# apple_all_pt2.net
KiCad netlist of a schematic drawn in EAGLE
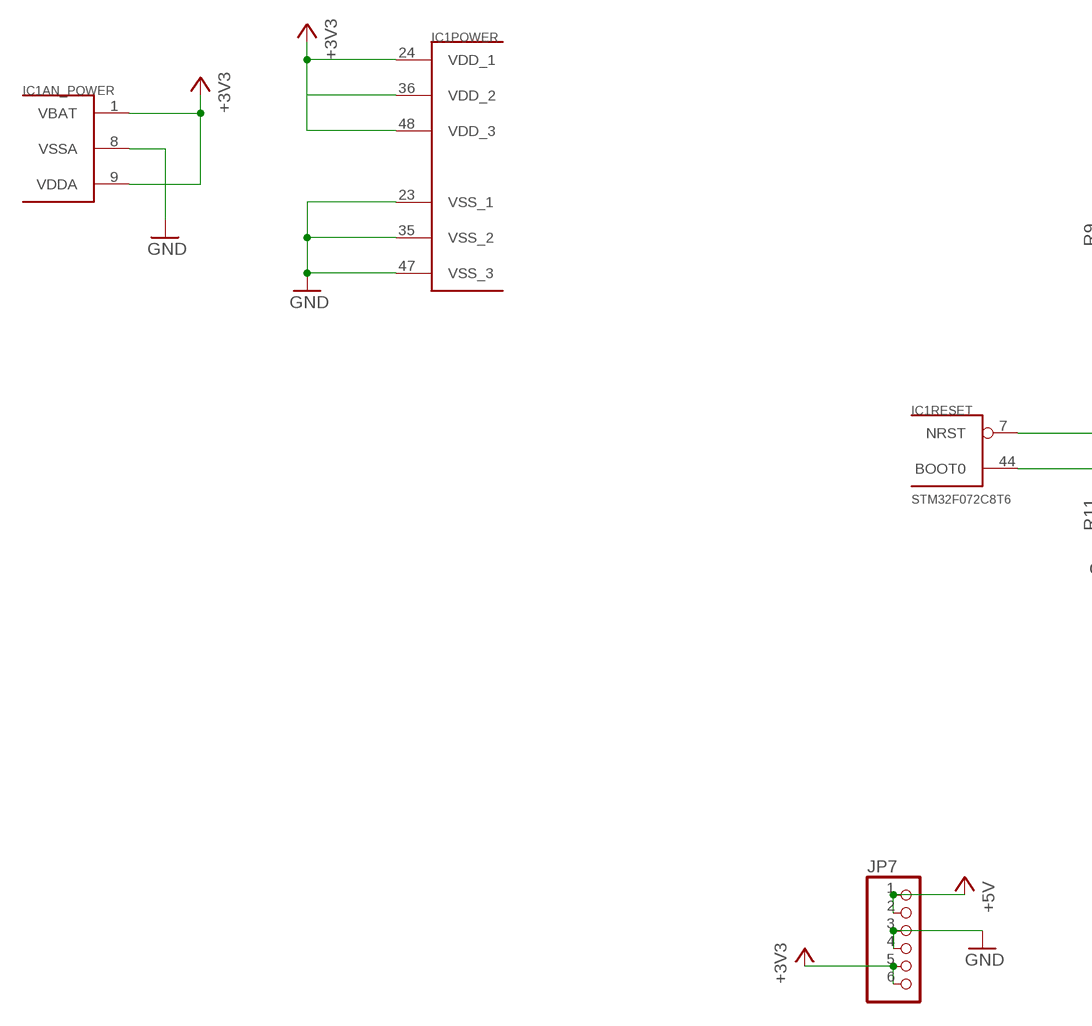
[diagram p0: schematic, sheet 1, part 1 of 2]
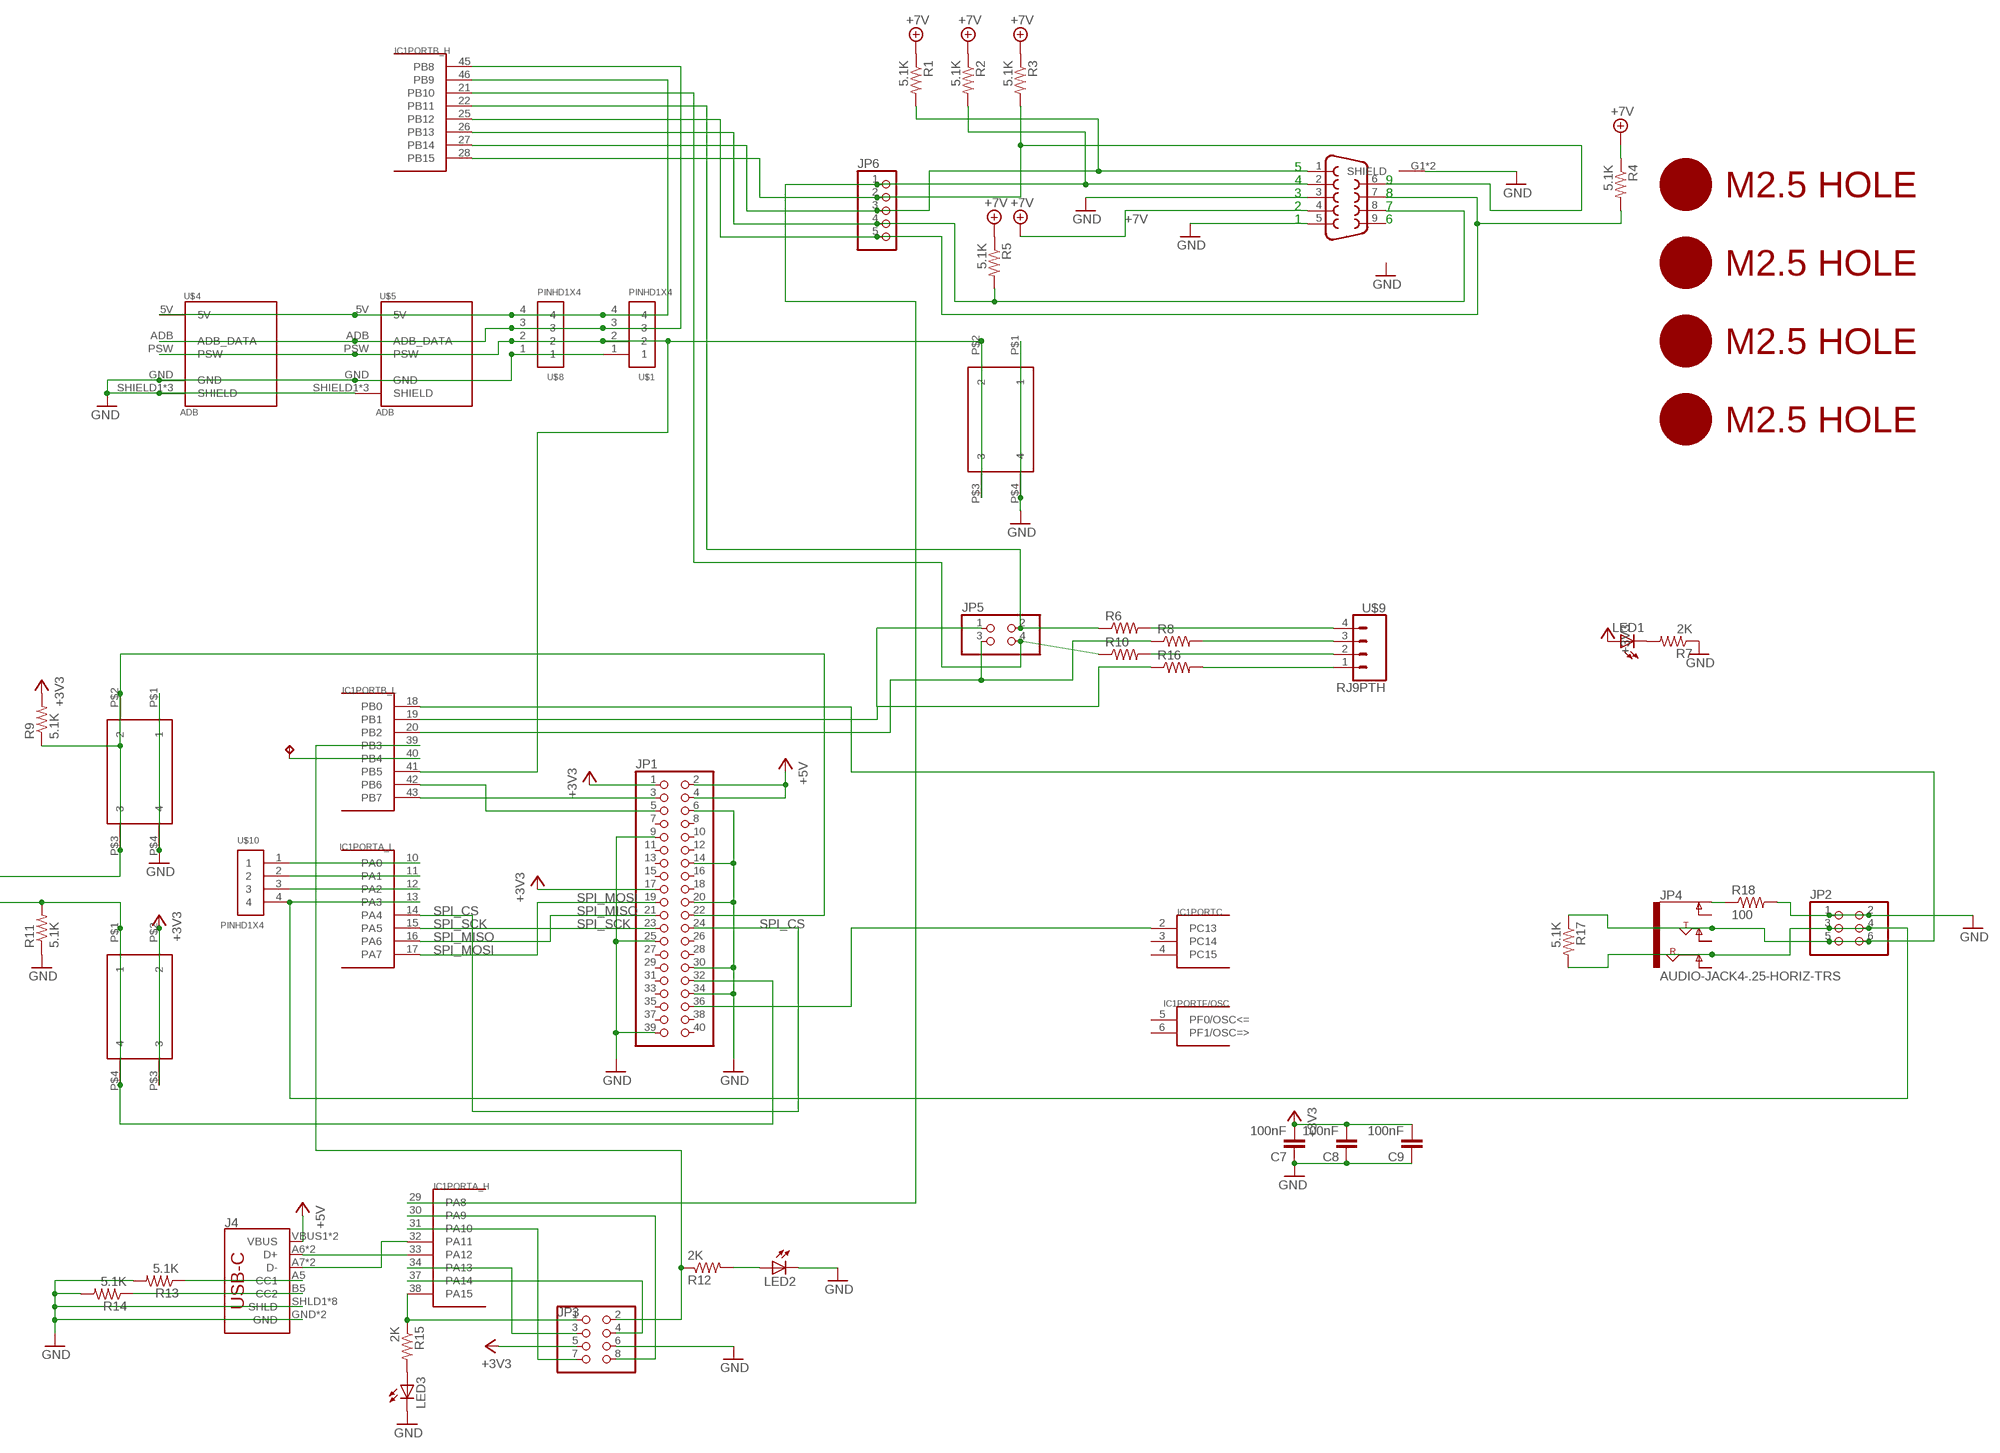
[diagram p1: schematic, sheet 1, part 2 of 2]

(export (version "E")
  (design (tool "Eeschema 10.0.6"))
  (components
    (comp (ref "C7")
      (value "100nF")
      (footprint "eagle-import:0805@1")
      (libsource (lib "eagle-import") (part "CAP0805"))
    )
    (comp (ref "C8")
      (value "100nF")
      (footprint "eagle-import:0805@1")
      (libsource (lib "eagle-import") (part "CAP0805"))
    )
    (comp (ref "C9")
      (value "100nF")
      (footprint "eagle-import:0805@1")
      (libsource (lib "eagle-import") (part "CAP0805"))
    )
    (comp (ref "IC1")
      (value "STM32F072C8T6")
      (footprint "eagle-import:TQFP48")
      (libsource (lib "eagle-import") (part "STM32F072C8T6"))
    )
    (comp (ref "J2")
      (value "DB9FEMALE")
      (footprint "eagle-import:DB9")
      (libsource (lib "eagle-import") (part "DB9FEMALE"))
    )
    (comp (ref "J4")
      (value "USB_C16PIN")
      (footprint "eagle-import:USB-C-16P")
      (libsource (lib "eagle-import") (part "USB_C16PIN"))
    )
    (comp (ref "JP1")
      (value "PINHD-2X20-BIG")
      (footprint "eagle-import:2X20-BIG")
      (libsource (lib "eagle-import") (part "PINHD-2X20-BIG"))
    )
    (comp (ref "JP2")
      (value "PINHD-2X3")
      (footprint "eagle-import:2X03")
      (libsource (lib "eagle-import") (part "PINHD-2X3"))
    )
    (comp (ref "JP3")
      (value "PINHD-2X4")
      (footprint "eagle-import:2X04")
      (libsource (lib "eagle-import") (part "PINHD-2X4"))
    )
    (comp (ref "JP4")
      (value "AUDIO-JACK4-.25-HORIZ-TRS")
      (footprint "eagle-import:AUDIO-JACK-.25-INCH-HORIZ-PTH")
      (libsource (lib "eagle-import") (part "AUDIO-JACK4-.25-HORIZ-TRS"))
    )
    (comp (ref "JP5")
      (value "PINHD-2X2")
      (footprint "eagle-import:2X02")
      (libsource (lib "eagle-import") (part "PINHD-2X2"))
    )
    (comp (ref "JP6")
      (value "PINHD-1X5")
      (footprint "eagle-import:1X05")
      (libsource (lib "eagle-import") (part "PINHD-1X5"))
    )
    (comp (ref "JP7")
      (value "PINHD-1X6CB")
      (footprint "eagle-import:1X06-CLEANBIG")
      (libsource (lib "eagle-import") (part "PINHD-1X6CB"))
    )
    (comp (ref "LED1")
      (value "LEDCHIP-LED0805")
      (footprint "eagle-import:CHIP-LED0805")
      (libsource (lib "eagle-import") (part "LEDCHIP-LED0805"))
    )
    (comp (ref "LED2")
      (value "LEDCHIP-LED0805")
      (footprint "eagle-import:CHIP-LED0805")
      (libsource (lib "eagle-import") (part "LEDCHIP-LED0805"))
    )
    (comp (ref "LED3")
      (value "LEDCHIP-LED0805")
      (footprint "eagle-import:CHIP-LED0805")
      (libsource (lib "eagle-import") (part "LEDCHIP-LED0805"))
    )
    (comp (ref "R1")
      (value "5.1K")
      (footprint "eagle-import:0805")
      (libsource (lib "eagle-import") (part "RESISTOR0805-RES"))
    )
    (comp (ref "R2")
      (value "5.1K")
      (footprint "eagle-import:0805")
      (libsource (lib "eagle-import") (part "RESISTOR0805-RES"))
    )
    (comp (ref "R3")
      (value "5.1K")
      (footprint "eagle-import:0805")
      (libsource (lib "eagle-import") (part "RESISTOR0805-RES"))
    )
    (comp (ref "R4")
      (value "5.1K")
      (footprint "eagle-import:0805")
      (libsource (lib "eagle-import") (part "RESISTOR0805-RES"))
    )
    (comp (ref "R5")
      (value "5.1K")
      (footprint "eagle-import:0805")
      (libsource (lib "eagle-import") (part "RESISTOR0805-RES"))
    )
    (comp (ref "R6")
      (value "50")
      (footprint "eagle-import:0805")
      (libsource (lib "eagle-import") (part "RESISTOR0805-RES"))
    )
    (comp (ref "R7")
      (value "2K")
      (footprint "eagle-import:0805")
      (libsource (lib "eagle-import") (part "RESISTOR0805-RES"))
    )
    (comp (ref "R8")
      (value "50")
      (footprint "eagle-import:0805")
      (libsource (lib "eagle-import") (part "RESISTOR0805-RES"))
    )
    (comp (ref "R9")
      (value "5.1K")
      (footprint "eagle-import:0805")
      (libsource (lib "eagle-import") (part "RESISTOR0805-RES"))
    )
    (comp (ref "R10")
      (value "50")
      (footprint "eagle-import:0805")
      (libsource (lib "eagle-import") (part "RESISTOR0805-RES"))
    )
    (comp (ref "R11")
      (value "5.1K")
      (footprint "eagle-import:0805")
      (libsource (lib "eagle-import") (part "RESISTOR0805-RES"))
    )
    (comp (ref "R12")
      (value "2K")
      (footprint "eagle-import:0805")
      (libsource (lib "eagle-import") (part "RESISTOR0805-RES"))
    )
    (comp (ref "R13")
      (value "5.1K")
      (footprint "eagle-import:0805")
      (libsource (lib "eagle-import") (part "RESISTOR0805-RES"))
    )
    (comp (ref "R14")
      (value "5.1K")
      (footprint "eagle-import:0805")
      (libsource (lib "eagle-import") (part "RESISTOR0805-RES"))
    )
    (comp (ref "R15")
      (value "2K")
      (footprint "eagle-import:0805")
      (libsource (lib "eagle-import") (part "RESISTOR0805-RES"))
    )
    (comp (ref "R16")
      (value "50")
      (footprint "eagle-import:0805")
      (libsource (lib "eagle-import") (part "RESISTOR0805-RES"))
    )
    (comp (ref "R17")
      (value "5.1K")
      (footprint "eagle-import:0805")
      (libsource (lib "eagle-import") (part "RESISTOR0805-RES"))
    )
    (comp (ref "R18")
      (value "100")
      (footprint "eagle-import:0805")
      (libsource (lib "eagle-import") (part "RESISTOR0805-RES"))
    )
    (comp (ref "SW1")
      (value "324_SW")
      (footprint "eagle-import:342_SWICH_FOOT")
      (libsource (lib "eagle-import") (part "324_SW"))
    )
    (comp (ref "SW2")
      (value "324_SW")
      (footprint "eagle-import:342_SWICH_FOOT")
      (libsource (lib "eagle-import") (part "324_SW"))
    )
    (comp (ref "SW3")
      (value "324_SW")
      (footprint "eagle-import:342_SWICH_FOOT")
      (libsource (lib "eagle-import") (part "324_SW"))
    )
    (comp (ref "TP3")
      (value "TPTP12R")
      (footprint "eagle-import:TP12R")
      (libsource (lib "eagle-import") (part "TPTP12R"))
    )
    (comp (ref "U$1")
      (value "PINHD1X4")
      (footprint "eagle-import:1X04-CLEANBIG")
      (libsource (lib "eagle-import") (part "PINHD1X4"))
    )
    (comp (ref "U$2")
      (value "M2.5HOLE")
      (footprint "eagle-import:M2.5HOLE")
      (libsource (lib "eagle-import") (part "M2.5HOLE"))
    )
    (comp (ref "U$3")
      (value "M2.5HOLE")
      (footprint "eagle-import:M2.5HOLE")
      (libsource (lib "eagle-import") (part "M2.5HOLE"))
    )
    (comp (ref "U$4")
      (value "ADB")
      (footprint "eagle-import:DIN4")
      (libsource (lib "eagle-import") (part "ADB"))
    )
    (comp (ref "U$5")
      (value "ADB")
      (footprint "eagle-import:DIN4")
      (libsource (lib "eagle-import") (part "ADB"))
    )
    (comp (ref "U$6")
      (value "M2.5HOLE")
      (footprint "eagle-import:M2.5HOLE")
      (libsource (lib "eagle-import") (part "M2.5HOLE"))
    )
    (comp (ref "U$7")
      (value "M2.5HOLE")
      (footprint "eagle-import:M2.5HOLE")
      (libsource (lib "eagle-import") (part "M2.5HOLE"))
    )
    (comp (ref "U$8")
      (value "PINHD1X4")
      (footprint "eagle-import:1X04-CLEANBIG")
      (libsource (lib "eagle-import") (part "PINHD1X4"))
    )
    (comp (ref "U$9")
      (value "RJ9PTH")
      (footprint "eagle-import:RJ9")
      (libsource (lib "eagle-import") (part "RJ9PTH"))
    )
    (comp (ref "U$10")
      (value "PINHD1X4")
      (footprint "eagle-import:1X04-CLEANBIG")
      (libsource (lib "eagle-import") (part "PINHD1X4"))
    )
  )
  (nets
    (net (code "1") (name "+3V3") (class "Default")
      (node (ref "C7") (pin "2") (pinfunction "2_2") (pintype "passive"))
      (node (ref "C8") (pin "2") (pinfunction "2_2") (pintype "passive"))
      (node (ref "C9") (pin "2") (pinfunction "2_2") (pintype "passive"))
      (node (ref "IC1") (pin "1") (pinfunction "VBAT_1") (pintype "power_in"))
      (node (ref "IC1") (pin "24") (pinfunction "VDD_1_24") (pintype "power_in"))
      (node (ref "IC1") (pin "36") (pinfunction "VDD_2_36") (pintype "power_in"))
      (node (ref "IC1") (pin "48") (pinfunction "VDD_3_48") (pintype "power_in"))
      (node (ref "IC1") (pin "9") (pinfunction "VDDA_9") (pintype "power_in"))
      (node (ref "JP1") (pin "1") (pinfunction "1_1") (pintype "passive"))
      (node (ref "JP1") (pin "17") (pinfunction "17_17") (pintype "passive"))
      (node (ref "JP3") (pin "5") (pinfunction "5_5") (pintype "passive"))
      (node (ref "JP7") (pin "5") (pinfunction "5_5") (pintype "passive"))
      (node (ref "JP7") (pin "6") (pinfunction "6_6") (pintype "passive"))
      (node (ref "LED1") (pin "A") (pinfunction "A_A") (pintype "passive"))
      (node (ref "R9") (pin "2") (pinfunction "2_2") (pintype "passive"))
      (node (ref "SW2") (pin "P$2") (pinfunction "2_P$2") (pintype "bidirectional"))
      (node (ref "SW2") (pin "P$3") (pinfunction "3_P$3") (pintype "bidirectional"))
    )
    (net (code "2") (name "+5V") (class "Default")
      (node (ref "J4") (pin "VBUS1") (pinfunction "VBUS_VBUS1") (pintype "bidirectional"))
      (node (ref "J4") (pin "VBUS2") (pinfunction "VBUS_VBUS2") (pintype "bidirectional"))
      (node (ref "JP1") (pin "2") (pinfunction "2_2") (pintype "passive"))
      (node (ref "JP1") (pin "4") (pinfunction "4_4") (pintype "passive"))
      (node (ref "JP7") (pin "1") (pinfunction "1_1") (pintype "passive"))
      (node (ref "JP7") (pin "2") (pinfunction "2_2") (pintype "passive"))
    )
    (net (code "3") (name "+7V") (class "Default")
      (node (ref "J2") (pin "4") (pinfunction "4_4") (pintype "passive"))
      (node (ref "R1") (pin "1") (pinfunction "1_1") (pintype "passive"))
      (node (ref "R2") (pin "1") (pinfunction "1_1") (pintype "passive"))
      (node (ref "R3") (pin "1") (pinfunction "1_1") (pintype "passive"))
      (node (ref "R4") (pin "1") (pinfunction "1_1") (pintype "passive"))
      (node (ref "R5") (pin "1") (pinfunction "1_1") (pintype "passive"))
    )
    (net (code "4") (name "/SPI_CS") (class "Default")
      (node (ref "IC1") (pin "14") (pinfunction "PA4_14") (pintype "bidirectional"))
      (node (ref "JP1") (pin "24") (pinfunction "24_24") (pintype "passive"))
    )
    (net (code "5") (name "/SPI_MISO") (class "Default")
      (node (ref "IC1") (pin "16") (pinfunction "PA6_16") (pintype "bidirectional"))
      (node (ref "JP1") (pin "21") (pinfunction "21_21") (pintype "passive"))
    )
    (net (code "6") (name "/SPI_MOSI") (class "Default")
      (node (ref "IC1") (pin "17") (pinfunction "PA7_17") (pintype "bidirectional"))
      (node (ref "JP1") (pin "19") (pinfunction "19_19") (pintype "passive"))
    )
    (net (code "7") (name "/SPI_SCK") (class "Default")
      (node (ref "IC1") (pin "15") (pinfunction "PA5_15") (pintype "bidirectional"))
      (node (ref "JP1") (pin "23") (pinfunction "23_23") (pintype "passive"))
    )
    (net (code "8") (name "GND") (class "Default")
      (node (ref "C7") (pin "1") (pinfunction "1_1") (pintype "passive"))
      (node (ref "C8") (pin "1") (pinfunction "1_1") (pintype "passive"))
      (node (ref "C9") (pin "1") (pinfunction "1_1") (pintype "passive"))
      (node (ref "IC1") (pin "23") (pinfunction "VSS_1_23") (pintype "power_in"))
      (node (ref "IC1") (pin "35") (pinfunction "VSS_2_35") (pintype "power_in"))
      (node (ref "IC1") (pin "47") (pinfunction "VSS_3_47") (pintype "power_in"))
      (node (ref "IC1") (pin "8") (pinfunction "VSSA_8") (pintype "power_in"))
      (node (ref "J2") (pin "3") (pinfunction "3_3") (pintype "passive"))
      (node (ref "J2") (pin "5") (pinfunction "5_5") (pintype "passive"))
      (node (ref "J2") (pin "G1") (pinfunction "SHIELD_G1") (pintype "bidirectional"))
      (node (ref "J2") (pin "G2") (pinfunction "SHIELD_G2") (pintype "bidirectional"))
      (node (ref "J4") (pin "GND") (pinfunction "GND_GND") (pintype "bidirectional"))
      (node (ref "J4") (pin "GND2") (pinfunction "GND_GND2") (pintype "bidirectional"))
      (node (ref "J4") (pin "SHLD1") (pinfunction "SHLD_SHLD1") (pintype "bidirectional"))
      (node (ref "J4") (pin "SHLD2") (pinfunction "SHLD_SHLD2") (pintype "bidirectional"))
      (node (ref "J4") (pin "SHLD3") (pinfunction "SHLD_SHLD3") (pintype "bidirectional"))
      (node (ref "J4") (pin "SHLD4") (pinfunction "SHLD_SHLD4") (pintype "bidirectional"))
      (node (ref "J4") (pin "SHLD5") (pinfunction "SHLD_SHLD5") (pintype "bidirectional"))
      (node (ref "J4") (pin "SHLD6") (pinfunction "SHLD_SHLD6") (pintype "bidirectional"))
      (node (ref "J4") (pin "SHLD7") (pinfunction "SHLD_SHLD7") (pintype "bidirectional"))
      (node (ref "J4") (pin "SHLD8") (pinfunction "SHLD_SHLD8") (pintype "bidirectional"))
      (node (ref "JP1") (pin "14") (pinfunction "14_14") (pintype "passive"))
      (node (ref "JP1") (pin "20") (pinfunction "20_20") (pintype "passive"))
      (node (ref "JP1") (pin "25") (pinfunction "25_25") (pintype "passive"))
      (node (ref "JP1") (pin "30") (pinfunction "30_30") (pintype "passive"))
      (node (ref "JP1") (pin "34") (pinfunction "34_34") (pintype "passive"))
      (node (ref "JP1") (pin "39") (pinfunction "39_39") (pintype "passive"))
      (node (ref "JP1") (pin "6") (pinfunction "6_6") (pintype "passive"))
      (node (ref "JP1") (pin "9") (pinfunction "9_9") (pintype "passive"))
      (node (ref "JP2") (pin "1") (pinfunction "1_1") (pintype "passive"))
      (node (ref "JP2") (pin "2") (pinfunction "2_2") (pintype "passive"))
      (node (ref "JP3") (pin "6") (pinfunction "6_6") (pintype "passive"))
      (node (ref "JP7") (pin "3") (pinfunction "3_3") (pintype "passive"))
      (node (ref "JP7") (pin "4") (pinfunction "4_4") (pintype "passive"))
      (node (ref "LED2") (pin "C") (pinfunction "C_C") (pintype "passive"))
      (node (ref "LED3") (pin "C") (pinfunction "C_C") (pintype "passive"))
      (node (ref "R11") (pin "1") (pinfunction "1_1") (pintype "passive"))
      (node (ref "R13") (pin "2") (pinfunction "2_2") (pintype "passive"))
      (node (ref "R14") (pin "2") (pinfunction "2_2") (pintype "passive"))
      (node (ref "R18") (pin "2") (pinfunction "2_2") (pintype "passive"))
      (node (ref "R7") (pin "1") (pinfunction "1_1") (pintype "passive"))
      (node (ref "SW1") (pin "P$1") (pinfunction "1_P$1") (pintype "bidirectional"))
      (node (ref "SW1") (pin "P$4") (pinfunction "4_P$4") (pintype "bidirectional"))
      (node (ref "SW3") (pin "P$1") (pinfunction "1_P$1") (pintype "bidirectional"))
      (node (ref "SW3") (pin "P$4") (pinfunction "4_P$4") (pintype "bidirectional"))
      (node (ref "U$1") (pin "1") (pinfunction "1_1") (pintype "bidirectional"))
      (node (ref "U$4") (pin "GND") (pinfunction "GND_GND") (pintype "bidirectional"))
      (node (ref "U$4") (pin "SHIELD1") (pinfunction "SHIELD_SHIELD1") (pintype "bidirectional"))
      (node (ref "U$4") (pin "SHIELD2") (pinfunction "SHIELD_SHIELD2") (pintype "bidirectional"))
      (node (ref "U$4") (pin "SHIELD3") (pinfunction "SHIELD_SHIELD3") (pintype "bidirectional"))
      (node (ref "U$5") (pin "GND") (pinfunction "GND_GND") (pintype "bidirectional"))
      (node (ref "U$5") (pin "SHIELD1") (pinfunction "SHIELD_SHIELD1") (pintype "bidirectional"))
      (node (ref "U$5") (pin "SHIELD2") (pinfunction "SHIELD_SHIELD2") (pintype "bidirectional"))
      (node (ref "U$5") (pin "SHIELD3") (pinfunction "SHIELD_SHIELD3") (pintype "bidirectional"))
      (node (ref "U$8") (pin "1") (pinfunction "1_1") (pintype "bidirectional"))
    )
    (net (code "9") (name "Net-(IC1B-PA8)") (class "Default")
      (node (ref "IC1") (pin "29") (pinfunction "PA8_29") (pintype "bidirectional"))
      (node (ref "J2") (pin "2") (pinfunction "2_2") (pintype "passive"))
      (node (ref "JP6") (pin "1") (pinfunction "1_1") (pintype "passive"))
      (node (ref "R2") (pin "2") (pinfunction "2_2") (pintype "passive"))
    )
    (net (code "10") (name "Net-(IC1B-PA9)") (class "Default")
      (node (ref "IC1") (pin "30") (pinfunction "PA9_30") (pintype "bidirectional"))
      (node (ref "JP3") (pin "8") (pinfunction "8_8") (pintype "passive"))
    )
    (net (code "11") (name "Net-(IC1B-PA10)") (class "Default")
      (node (ref "IC1") (pin "31") (pinfunction "PA10_31") (pintype "bidirectional"))
      (node (ref "JP3") (pin "7") (pinfunction "7_7") (pintype "passive"))
    )
    (net (code "12") (name "Net-(IC1B-PA11)") (class "Default")
      (node (ref "IC1") (pin "32") (pinfunction "PA11_32") (pintype "bidirectional"))
      (node (ref "J4") (pin "A7") (pinfunction "D-_A7") (pintype "bidirectional"))
      (node (ref "J4") (pin "B7") (pinfunction "D-_B7") (pintype "bidirectional"))
    )
    (net (code "13") (name "Net-(IC1B-PA12)") (class "Default")
      (node (ref "IC1") (pin "33") (pinfunction "PA12_33") (pintype "bidirectional"))
      (node (ref "J4") (pin "A6") (pinfunction "D+_A6") (pintype "bidirectional"))
      (node (ref "J4") (pin "B6") (pinfunction "D+_B6") (pintype "bidirectional"))
    )
    (net (code "14") (name "Net-(IC1B-PA13)") (class "Default")
      (node (ref "IC1") (pin "34") (pinfunction "PA13_34") (pintype "bidirectional"))
      (node (ref "JP3") (pin "3") (pinfunction "3_3") (pintype "passive"))
    )
    (net (code "15") (name "Net-(IC1B-PA14)") (class "Default")
      (node (ref "IC1") (pin "37") (pinfunction "PA14_37") (pintype "bidirectional"))
      (node (ref "JP3") (pin "4") (pinfunction "4_4") (pintype "passive"))
    )
    (net (code "16") (name "Net-(IC1B-PA15)") (class "Default")
      (node (ref "IC1") (pin "38") (pinfunction "PA15_38") (pintype "bidirectional"))
      (node (ref "JP3") (pin "1") (pinfunction "1_1") (pintype "passive"))
      (node (ref "R15") (pin "1") (pinfunction "1_1") (pintype "passive"))
    )
    (net (code "17") (name "Net-(IC1C-PA0)") (class "Default")
      (node (ref "IC1") (pin "10") (pinfunction "PA0_10") (pintype "bidirectional"))
      (node (ref "U$10") (pin "1") (pinfunction "1_1") (pintype "bidirectional"))
    )
    (net (code "18") (name "Net-(IC1C-PA1)") (class "Default")
      (node (ref "IC1") (pin "11") (pinfunction "PA1_11") (pintype "bidirectional"))
      (node (ref "U$10") (pin "2") (pinfunction "2_2") (pintype "bidirectional"))
    )
    (net (code "19") (name "Net-(IC1C-PA2)") (class "Default")
      (node (ref "IC1") (pin "12") (pinfunction "PA2_12") (pintype "bidirectional"))
      (node (ref "U$10") (pin "3") (pinfunction "3_3") (pintype "bidirectional"))
    )
    (net (code "20") (name "Net-(IC1C-PA3)") (class "Default")
      (node (ref "IC1") (pin "13") (pinfunction "PA3_13") (pintype "bidirectional"))
      (node (ref "JP2") (pin "3") (pinfunction "3_3") (pintype "passive"))
      (node (ref "JP2") (pin "4") (pinfunction "4_4") (pintype "passive"))
      (node (ref "JP4") (pin "RING") (pinfunction "RING_RING") (pintype "bidirectional"))
      (node (ref "R17") (pin "2") (pinfunction "2_2") (pintype "passive"))
      (node (ref "U$10") (pin "4") (pinfunction "4_4") (pintype "bidirectional"))
    )
    (net (code "21") (name "Net-(IC1D-PB8)") (class "Default")
      (node (ref "IC1") (pin "45") (pinfunction "PB8_45") (pintype "bidirectional"))
      (node (ref "U$1") (pin "3") (pinfunction "3_3") (pintype "bidirectional"))
      (node (ref "U$4") (pin "ADB") (pinfunction "ADB_DATA_ADB") (pintype "bidirectional"))
      (node (ref "U$5") (pin "ADB") (pinfunction "ADB_DATA_ADB") (pintype "bidirectional"))
      (node (ref "U$8") (pin "3") (pinfunction "3_3") (pintype "bidirectional"))
    )
    (net (code "22") (name "Net-(IC1D-PB9)") (class "Default")
      (node (ref "IC1") (pin "46") (pinfunction "PB9_46") (pintype "bidirectional"))
      (node (ref "U$1") (pin "4") (pinfunction "4_4") (pintype "bidirectional"))
      (node (ref "U$4") (pin "5V") (pinfunction "5V_5V") (pintype "bidirectional"))
      (node (ref "U$5") (pin "5V") (pinfunction "5V_5V") (pintype "bidirectional"))
      (node (ref "U$8") (pin "4") (pinfunction "4_4") (pintype "bidirectional"))
    )
    (net (code "23") (name "Net-(IC1D-PB10)") (class "Default")
      (node (ref "IC1") (pin "21") (pinfunction "PB10_21") (pintype "bidirectional"))
      (node (ref "JP5") (pin "4") (pinfunction "4_4") (pintype "passive"))
      (node (ref "R10") (pin "1") (pinfunction "1_1") (pintype "passive"))
    )
    (net (code "24") (name "Net-(IC1D-PB11)") (class "Default")
      (node (ref "IC1") (pin "22") (pinfunction "PB11_22") (pintype "bidirectional"))
      (node (ref "JP5") (pin "2") (pinfunction "2_2") (pintype "passive"))
      (node (ref "R6") (pin "1") (pinfunction "1_1") (pintype "passive"))
    )
    (net (code "25") (name "Net-(IC1D-PB12)") (class "Default")
      (node (ref "IC1") (pin "25") (pinfunction "PB12_25") (pintype "bidirectional"))
      (node (ref "J2") (pin "7") (pinfunction "7_7") (pintype "passive"))
      (node (ref "JP6") (pin "5") (pinfunction "5_5") (pintype "passive"))
      (node (ref "R4") (pin "2") (pinfunction "2_2") (pintype "passive"))
    )
    (net (code "26") (name "Net-(IC1D-PB13)") (class "Default")
      (node (ref "IC1") (pin "26") (pinfunction "PB13_26") (pintype "bidirectional"))
      (node (ref "J2") (pin "8") (pinfunction "8_8") (pintype "passive"))
      (node (ref "JP6") (pin "4") (pinfunction "4_4") (pintype "passive"))
      (node (ref "R5") (pin "2") (pinfunction "2_2") (pintype "passive"))
    )
    (net (code "27") (name "Net-(IC1D-PB14)") (class "Default")
      (node (ref "IC1") (pin "27") (pinfunction "PB14_27") (pintype "bidirectional"))
      (node (ref "J2") (pin "1") (pinfunction "1_1") (pintype "passive"))
      (node (ref "JP6") (pin "3") (pinfunction "3_3") (pintype "passive"))
      (node (ref "R1") (pin "2") (pinfunction "2_2") (pintype "passive"))
    )
    (net (code "28") (name "Net-(IC1D-PB15)") (class "Default")
      (node (ref "IC1") (pin "28") (pinfunction "PB15_28") (pintype "bidirectional"))
      (node (ref "J2") (pin "6") (pinfunction "6_6") (pintype "passive"))
      (node (ref "JP6") (pin "2") (pinfunction "2_2") (pintype "passive"))
      (node (ref "R3") (pin "2") (pinfunction "2_2") (pintype "passive"))
    )
    (net (code "29") (name "Net-(IC1E-PB0)") (class "Default")
      (node (ref "IC1") (pin "18") (pinfunction "PB0_18") (pintype "bidirectional"))
      (node (ref "JP2") (pin "5") (pinfunction "5_5") (pintype "passive"))
      (node (ref "JP2") (pin "6") (pinfunction "6_6") (pintype "passive"))
      (node (ref "JP4") (pin "TIP") (pinfunction "TIP_TIP") (pintype "bidirectional"))
      (node (ref "R17") (pin "1") (pinfunction "1_1") (pintype "passive"))
    )
    (net (code "30") (name "Net-(IC1E-PB1)") (class "Default")
      (node (ref "IC1") (pin "19") (pinfunction "PB1_19") (pintype "bidirectional"))
      (node (ref "JP5") (pin "1") (pinfunction "1_1") (pintype "passive"))
      (node (ref "R16") (pin "1") (pinfunction "1_1") (pintype "passive"))
    )
    (net (code "31") (name "Net-(IC1E-PB2)") (class "Default")
      (node (ref "IC1") (pin "20") (pinfunction "PB2_20") (pintype "bidirectional"))
      (node (ref "JP5") (pin "3") (pinfunction "3_3") (pintype "passive"))
      (node (ref "R8") (pin "1") (pinfunction "1_1") (pintype "passive"))
    )
    (net (code "32") (name "Net-(IC1E-PB3)") (class "Default")
      (node (ref "IC1") (pin "39") (pinfunction "PB3_39") (pintype "bidirectional"))
      (node (ref "JP3") (pin "2") (pinfunction "2_2") (pintype "passive"))
      (node (ref "R12") (pin "1") (pinfunction "1_1") (pintype "passive"))
    )
    (net (code "33") (name "Net-(IC1E-PB4)") (class "Default")
      (node (ref "IC1") (pin "40") (pinfunction "PB4_40") (pintype "bidirectional"))
      (node (ref "TP3") (pin "TP") (pinfunction "TP_TP") (pintype "input"))
    )
    (net (code "34") (name "Net-(IC1E-PB5)") (class "Default")
      (node (ref "IC1") (pin "41") (pinfunction "PB5_41") (pintype "bidirectional"))
      (node (ref "SW3") (pin "P$2") (pinfunction "2_P$2") (pintype "bidirectional"))
      (node (ref "SW3") (pin "P$3") (pinfunction "3_P$3") (pintype "bidirectional"))
      (node (ref "U$1") (pin "2") (pinfunction "2_2") (pintype "bidirectional"))
      (node (ref "U$4") (pin "PSW") (pinfunction "PSW_PSW") (pintype "bidirectional"))
      (node (ref "U$5") (pin "PSW") (pinfunction "PSW_PSW") (pintype "bidirectional"))
      (node (ref "U$8") (pin "2") (pinfunction "2_2") (pintype "bidirectional"))
    )
    (net (code "35") (name "Net-(IC1E-PB6)") (class "Default")
      (node (ref "IC1") (pin "42") (pinfunction "PB6_42") (pintype "bidirectional"))
      (node (ref "JP1") (pin "5") (pinfunction "5_5") (pintype "passive"))
    )
    (net (code "36") (name "Net-(IC1E-PB7)") (class "Default")
      (node (ref "IC1") (pin "43") (pinfunction "PB7_43") (pintype "bidirectional"))
      (node (ref "JP1") (pin "3") (pinfunction "3_3") (pintype "passive"))
    )
    (net (code "37") (name "Net-(IC1F-PC13)") (class "Default")
      (node (ref "IC1") (pin "2") (pinfunction "PC13_2") (pintype "bidirectional"))
      (node (ref "JP1") (pin "36") (pinfunction "36_36") (pintype "passive"))
    )
    (net (code "38") (name "Net-(IC1I-BOOT0)") (class "Default")
      (node (ref "IC1") (pin "44") (pinfunction "BOOT0_44") (pintype "input"))
      (node (ref "JP1") (pin "32") (pinfunction "32_32") (pintype "passive"))
      (node (ref "R11") (pin "2") (pinfunction "2_2") (pintype "passive"))
      (node (ref "SW2") (pin "P$1") (pinfunction "1_P$1") (pintype "bidirectional"))
      (node (ref "SW2") (pin "P$4") (pinfunction "4_P$4") (pintype "bidirectional"))
    )
    (net (code "39") (name "Net-(IC1I-NRST)") (class "Default")
      (node (ref "IC1") (pin "7") (pinfunction "NRST_7") (pintype "input"))
      (node (ref "JP1") (pin "22") (pinfunction "22_22") (pintype "passive"))
      (node (ref "R9") (pin "1") (pinfunction "1_1") (pintype "passive"))
      (node (ref "SW1") (pin "P$2") (pinfunction "2_P$2") (pintype "bidirectional"))
      (node (ref "SW1") (pin "P$3") (pinfunction "3_P$3") (pintype "bidirectional"))
    )
    (net (code "40") (name "Net-(J4-CC1)") (class "Default")
      (node (ref "J4") (pin "A5") (pinfunction "CC1_A5") (pintype "bidirectional"))
      (node (ref "R13") (pin "1") (pinfunction "1_1") (pintype "passive"))
    )
    (net (code "41") (name "Net-(J4-CC2)") (class "Default")
      (node (ref "J4") (pin "B5") (pinfunction "CC2_B5") (pintype "bidirectional"))
      (node (ref "R14") (pin "1") (pinfunction "1_1") (pintype "passive"))
    )
    (net (code "42") (name "Net-(JP4-EARTH)") (class "Default")
      (node (ref "JP4") (pin "SLEEVE") (pinfunction "EARTH_SLEEVE") (pintype "bidirectional"))
      (node (ref "R18") (pin "1") (pinfunction "1_1") (pintype "passive"))
    )
    (net (code "43") (name "Net-(LED1-PadC)") (class "Default")
      (node (ref "LED1") (pin "C") (pinfunction "C_C") (pintype "passive"))
      (node (ref "R7") (pin "2") (pinfunction "2_2") (pintype "passive"))
    )
    (net (code "44") (name "Net-(LED2-PadA)") (class "Default")
      (node (ref "LED2") (pin "A") (pinfunction "A_A") (pintype "passive"))
      (node (ref "R12") (pin "2") (pinfunction "2_2") (pintype "passive"))
    )
    (net (code "45") (name "Net-(LED3-PadA)") (class "Default")
      (node (ref "LED3") (pin "A") (pinfunction "A_A") (pintype "passive"))
      (node (ref "R15") (pin "2") (pinfunction "2_2") (pintype "passive"))
    )
    (net (code "46") (name "Net-(R6-Pad2)") (class "Default")
      (node (ref "R6") (pin "2") (pinfunction "2_2") (pintype "passive"))
      (node (ref "U$9") (pin "4") (pinfunction "4_4") (pintype "passive"))
    )
    (net (code "47") (name "Net-(R8-Pad2)") (class "Default")
      (node (ref "R8") (pin "2") (pinfunction "2_2") (pintype "passive"))
      (node (ref "U$9") (pin "3") (pinfunction "3_3") (pintype "passive"))
    )
    (net (code "48") (name "Net-(R10-Pad2)") (class "Default")
      (node (ref "R10") (pin "2") (pinfunction "2_2") (pintype "passive"))
      (node (ref "U$9") (pin "2") (pinfunction "2_2") (pintype "passive"))
    )
    (net (code "49") (name "Net-(R16-Pad2)") (class "Default")
      (node (ref "R16") (pin "2") (pinfunction "2_2") (pintype "passive"))
      (node (ref "U$9") (pin "1") (pinfunction "1_1") (pintype "passive"))
    )
    (net (code "50") (name "unconnected-(IC1F-PC14-Pad3)") (class "Default")
      (node (ref "IC1") (pin "3") (pinfunction "PC14_3") (pintype "bidirectional"))
    )
    (net (code "51") (name "unconnected-(IC1F-PC15-Pad4)") (class "Default")
      (node (ref "IC1") (pin "4") (pinfunction "PC15_4") (pintype "bidirectional"))
    )
    (net (code "52") (name "unconnected-(IC1G-PF0{slash}OSC<=-Pad5)") (class "Default")
      (node (ref "IC1") (pin "5") (pinfunction "PF0/OSC<=_5") (pintype "bidirectional"))
    )
    (net (code "53") (name "unconnected-(IC1G-PF1{slash}OSC=>-Pad6)") (class "Default")
      (node (ref "IC1") (pin "6") (pinfunction "PF1/OSC=>_6") (pintype "bidirectional"))
    )
    (net (code "54") (name "unconnected-(J2-Pad9)") (class "Default")
      (node (ref "J2") (pin "9") (pinfunction "9_9") (pintype "passive"))
    )
    (net (code "55") (name "unconnected-(JP1-Pad7)") (class "Default")
      (node (ref "JP1") (pin "7") (pinfunction "7_7") (pintype "passive"))
    )
    (net (code "56") (name "unconnected-(JP1-Pad8)") (class "Default")
      (node (ref "JP1") (pin "8") (pinfunction "8_8") (pintype "passive"))
    )
    (net (code "57") (name "unconnected-(JP1-Pad10)") (class "Default")
      (node (ref "JP1") (pin "10") (pinfunction "10_10") (pintype "passive"))
    )
    (net (code "58") (name "unconnected-(JP1-Pad11)") (class "Default")
      (node (ref "JP1") (pin "11") (pinfunction "11_11") (pintype "passive"))
    )
    (net (code "59") (name "unconnected-(JP1-Pad12)") (class "Default")
      (node (ref "JP1") (pin "12") (pinfunction "12_12") (pintype "passive"))
    )
    (net (code "60") (name "unconnected-(JP1-Pad13)") (class "Default")
      (node (ref "JP1") (pin "13") (pinfunction "13_13") (pintype "passive"))
    )
    (net (code "61") (name "unconnected-(JP1-Pad15)") (class "Default")
      (node (ref "JP1") (pin "15") (pinfunction "15_15") (pintype "passive"))
    )
    (net (code "62") (name "unconnected-(JP1-Pad16)") (class "Default")
      (node (ref "JP1") (pin "16") (pinfunction "16_16") (pintype "passive"))
    )
    (net (code "63") (name "unconnected-(JP1-Pad18)") (class "Default")
      (node (ref "JP1") (pin "18") (pinfunction "18_18") (pintype "passive"))
    )
    (net (code "64") (name "unconnected-(JP1-Pad26)") (class "Default")
      (node (ref "JP1") (pin "26") (pinfunction "26_26") (pintype "passive"))
    )
    (net (code "65") (name "unconnected-(JP1-Pad27)") (class "Default")
      (node (ref "JP1") (pin "27") (pinfunction "27_27") (pintype "passive"))
    )
    (net (code "66") (name "unconnected-(JP1-Pad28)") (class "Default")
      (node (ref "JP1") (pin "28") (pinfunction "28_28") (pintype "passive"))
    )
    (net (code "67") (name "unconnected-(JP1-Pad29)") (class "Default")
      (node (ref "JP1") (pin "29") (pinfunction "29_29") (pintype "passive"))
    )
    (net (code "68") (name "unconnected-(JP1-Pad31)") (class "Default")
      (node (ref "JP1") (pin "31") (pinfunction "31_31") (pintype "passive"))
    )
    (net (code "69") (name "unconnected-(JP1-Pad33)") (class "Default")
      (node (ref "JP1") (pin "33") (pinfunction "33_33") (pintype "passive"))
    )
    (net (code "70") (name "unconnected-(JP1-Pad35)") (class "Default")
      (node (ref "JP1") (pin "35") (pinfunction "35_35") (pintype "passive"))
    )
    (net (code "71") (name "unconnected-(JP1-Pad37)") (class "Default")
      (node (ref "JP1") (pin "37") (pinfunction "37_37") (pintype "passive"))
    )
    (net (code "72") (name "unconnected-(JP1-Pad38)") (class "Default")
      (node (ref "JP1") (pin "38") (pinfunction "38_38") (pintype "passive"))
    )
    (net (code "73") (name "unconnected-(JP1-Pad40)") (class "Default")
      (node (ref "JP1") (pin "40") (pinfunction "40_40") (pintype "passive"))
    )
    (net (code "74") (name "unconnected-(JP4-EARTH-NORM-PadSLEEVE-NORM)") (class "Default")
      (node (ref "JP4") (pin "SLEEVE-NORM") (pinfunction "EARTH-NORM_SLEEVE-NORM") (pintype "bidirectional"))
    )
    (net (code "75") (name "unconnected-(JP4-PadRING-NORM)") (class "Default")
      (node (ref "JP4") (pin "RING-NORM") (pinfunction "RING-NORM_RING-NORM") (pintype "bidirectional"))
    )
    (net (code "76") (name "unconnected-(JP4-PadTIP-NORM)") (class "Default")
      (node (ref "JP4") (pin "TIP-NORM") (pinfunction "TIP-NORM_TIP-NORM") (pintype "bidirectional"))
    )
  )
)
